# 3bpV2A_Opt.net
KiCad netlist of a schematic drawn in EAGLE
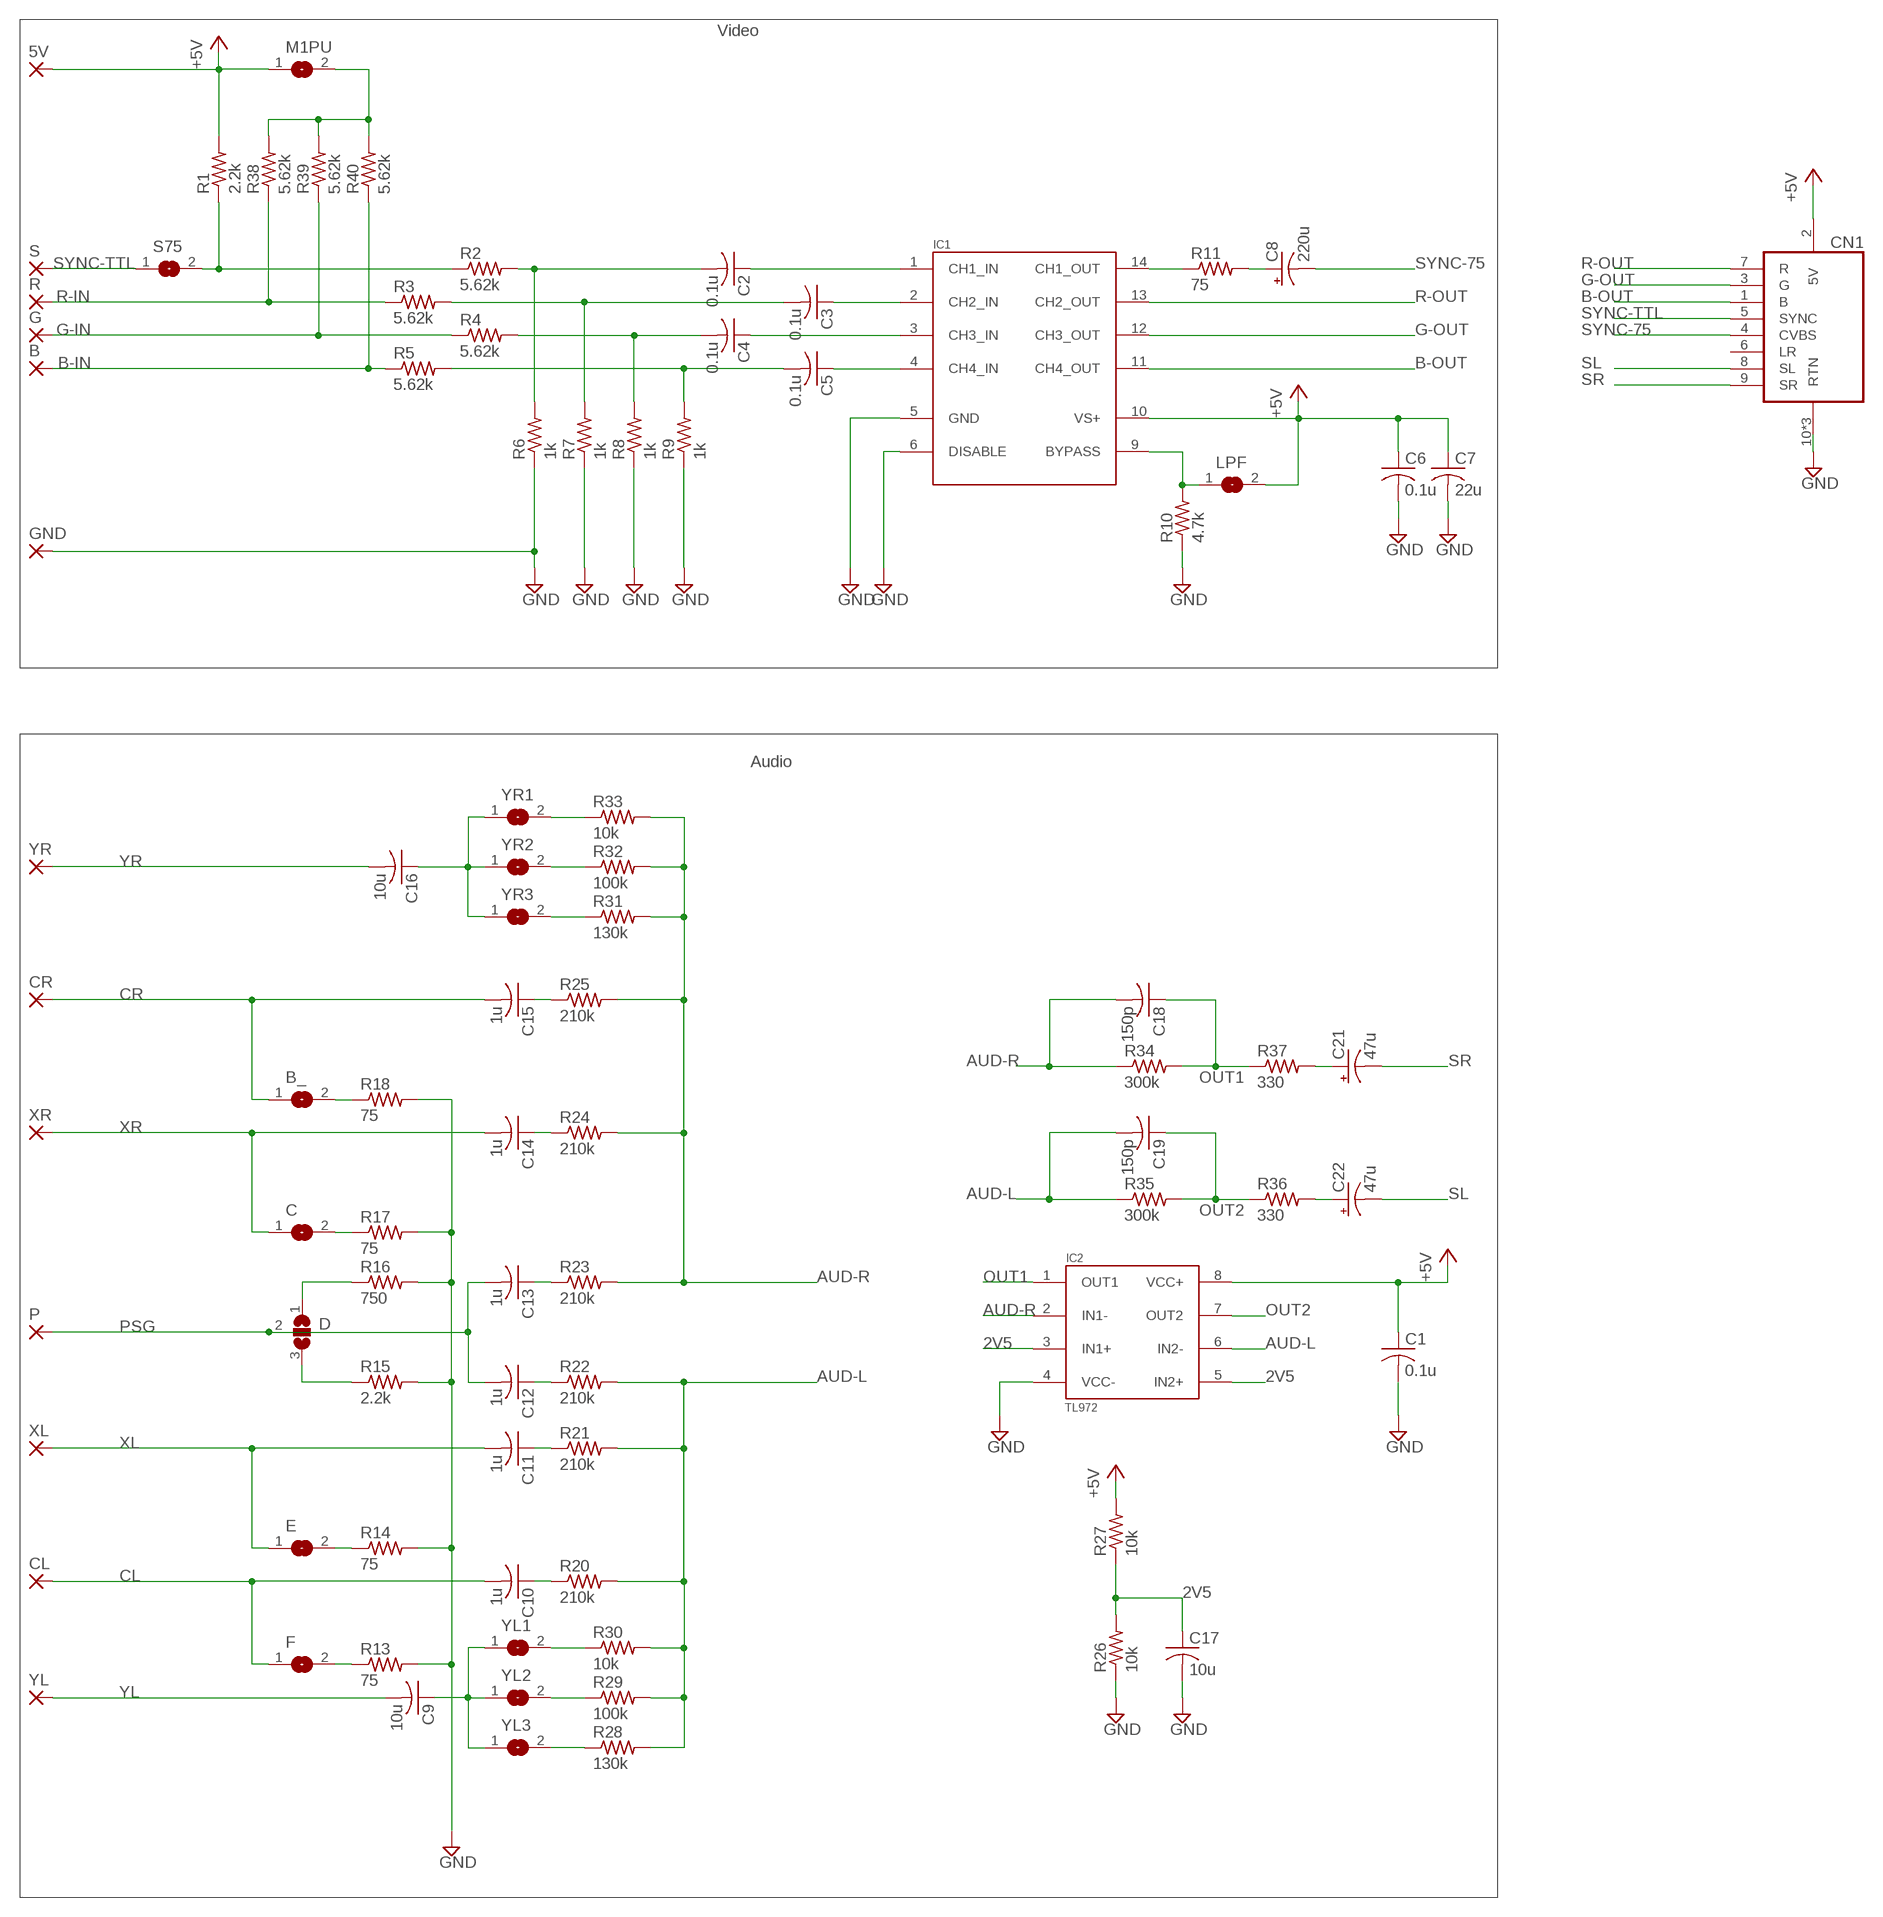
[diagram p0: schematic, sheet 1]

(export (version "E")
  (design (tool "Eeschema 10.0.6"))
  (components
    (comp (ref "5V")
      (value "SMD2")
      (footprint "eagle-import:SMD1,27-2,54")
      (libsource (lib "eagle-import") (part "SMD2"))
    )
    (comp (ref "B")
      (value "SMD2")
      (footprint "eagle-import:SMD1,27-2,54")
      (libsource (lib "eagle-import") (part "SMD2"))
    )
    (comp (ref "B_")
      (value "SMD_J")
      (footprint "eagle-import:SJ")
      (libsource (lib "eagle-import") (part "SMD_J"))
    )
    (comp (ref "C")
      (value "SMD_J")
      (footprint "eagle-import:SJ")
      (libsource (lib "eagle-import") (part "SMD_J"))
    )
    (comp (ref "C1")
      (value "0.1u")
      (footprint "eagle-import:C0603")
      (libsource (lib "eagle-import") (part "C-USC0603"))
    )
    (comp (ref "C2")
      (value "0.1u")
      (footprint "eagle-import:C0603")
      (libsource (lib "eagle-import") (part "C-USC0603"))
    )
    (comp (ref "C3")
      (value "0.1u")
      (footprint "eagle-import:C0603")
      (libsource (lib "eagle-import") (part "C-USC0603"))
    )
    (comp (ref "C4")
      (value "0.1u")
      (footprint "eagle-import:C0603")
      (libsource (lib "eagle-import") (part "C-USC0603"))
    )
    (comp (ref "C5")
      (value "0.1u")
      (footprint "eagle-import:C0603")
      (libsource (lib "eagle-import") (part "C-USC0603"))
    )
    (comp (ref "C6")
      (value "0.1u")
      (footprint "eagle-import:C0603")
      (libsource (lib "eagle-import") (part "C-USC0603"))
    )
    (comp (ref "C7")
      (value "22u")
      (footprint "eagle-import:C1206")
      (libsource (lib "eagle-import") (part "C-USC1206"))
    )
    (comp (ref "C8")
      (value "220u")
      (footprint "eagle-import:CT3528")
      (libsource (lib "eagle-import") (part "CPOL-USCT3528"))
    )
    (comp (ref "C9")
      (value "10u")
      (footprint "eagle-import:C0805")
      (libsource (lib "eagle-import") (part "C-USC0805"))
    )
    (comp (ref "C10")
      (value "1u")
      (footprint "eagle-import:C0603")
      (libsource (lib "eagle-import") (part "C-USC0603"))
    )
    (comp (ref "C11")
      (value "1u")
      (footprint "eagle-import:C0603")
      (libsource (lib "eagle-import") (part "C-USC0603"))
    )
    (comp (ref "C12")
      (value "1u")
      (footprint "eagle-import:C0603")
      (libsource (lib "eagle-import") (part "C-USC0603"))
    )
    (comp (ref "C13")
      (value "1u")
      (footprint "eagle-import:C0603")
      (libsource (lib "eagle-import") (part "C-USC0603"))
    )
    (comp (ref "C14")
      (value "1u")
      (footprint "eagle-import:C0603")
      (libsource (lib "eagle-import") (part "C-USC0603"))
    )
    (comp (ref "C15")
      (value "1u")
      (footprint "eagle-import:C0603")
      (libsource (lib "eagle-import") (part "C-USC0603"))
    )
    (comp (ref "C16")
      (value "10u")
      (footprint "eagle-import:C0805")
      (libsource (lib "eagle-import") (part "C-USC0805"))
    )
    (comp (ref "C17")
      (value "10u")
      (footprint "eagle-import:C1206")
      (libsource (lib "eagle-import") (part "C-USC1206"))
    )
    (comp (ref "C18")
      (value "150p")
      (footprint "eagle-import:C0603")
      (libsource (lib "eagle-import") (part "C-USC0603"))
    )
    (comp (ref "C19")
      (value "150p")
      (footprint "eagle-import:C0603")
      (libsource (lib "eagle-import") (part "C-USC0603"))
    )
    (comp (ref "C21")
      (value "47u")
      (footprint "eagle-import:CT3528")
      (libsource (lib "eagle-import") (part "CPOL-USCT3528"))
    )
    (comp (ref "C22")
      (value "47u")
      (footprint "eagle-import:CT3528")
      (libsource (lib "eagle-import") (part "CPOL-USCT3528"))
    )
    (comp (ref "CL")
      (value "SMD2")
      (footprint "eagle-import:SMD1,27-2,54")
      (libsource (lib "eagle-import") (part "SMD2"))
    )
    (comp (ref "CN1")
      (value "MD-90SM")
      (footprint "eagle-import:MD90SM")
      (libsource (lib "eagle-import") (part "MD-90SM"))
    )
    (comp (ref "CR")
      (value "SMD2")
      (footprint "eagle-import:SMD1,27-2,54")
      (libsource (lib "eagle-import") (part "SMD2"))
    )
    (comp (ref "D")
      (value "SMD_J2")
      (footprint "eagle-import:SJ_2")
      (libsource (lib "eagle-import") (part "SMD_J2"))
    )
    (comp (ref "E")
      (value "SMD_J")
      (footprint "eagle-import:SJ")
      (libsource (lib "eagle-import") (part "SMD_J"))
    )
    (comp (ref "F")
      (value "SMD_J")
      (footprint "eagle-import:SJ")
      (libsource (lib "eagle-import") (part "SMD_J"))
    )
    (comp (ref "G")
      (value "SMD2")
      (footprint "eagle-import:SMD1,27-2,54")
      (libsource (lib "eagle-import") (part "SMD2"))
    )
    (comp (ref "GND")
      (value "SMD2")
      (footprint "eagle-import:SMD1,27-2,54")
      (libsource (lib "eagle-import") (part "SMD2"))
    )
    (comp (ref "IC1")
      (value "THS7374IPWR")
      (footprint "eagle-import:TSSOP14")
      (libsource (lib "eagle-import") (part "THS7374IPWR"))
    )
    (comp (ref "IC2")
      (value "TL972")
      (footprint "eagle-import:SOIC8")
      (libsource (lib "eagle-import") (part "TL972"))
    )
    (comp (ref "LPF")
      (value "SMD_J")
      (footprint "eagle-import:SJ")
      (libsource (lib "eagle-import") (part "SMD_J"))
    )
    (comp (ref "M1PU")
      (value "SMD_J")
      (footprint "eagle-import:SJ")
      (libsource (lib "eagle-import") (part "SMD_J"))
    )
    (comp (ref "P")
      (value "SMD2")
      (footprint "eagle-import:SMD1,27-2,54")
      (libsource (lib "eagle-import") (part "SMD2"))
    )
    (comp (ref "R")
      (value "SMD2")
      (footprint "eagle-import:SMD1,27-2,54")
      (libsource (lib "eagle-import") (part "SMD2"))
    )
    (comp (ref "R1")
      (value "2.2k")
      (footprint "eagle-import:R0603")
      (libsource (lib "eagle-import") (part "R-US_R0603"))
    )
    (comp (ref "R2")
      (value "5.62k")
      (footprint "eagle-import:R0603")
      (libsource (lib "eagle-import") (part "R-US_R0603"))
    )
    (comp (ref "R3")
      (value "5.62k")
      (footprint "eagle-import:R0603")
      (libsource (lib "eagle-import") (part "R-US_R0603"))
    )
    (comp (ref "R4")
      (value "5.62k")
      (footprint "eagle-import:R0603")
      (libsource (lib "eagle-import") (part "R-US_R0603"))
    )
    (comp (ref "R5")
      (value "5.62k")
      (footprint "eagle-import:R0603")
      (libsource (lib "eagle-import") (part "R-US_R0603"))
    )
    (comp (ref "R6")
      (value "1k")
      (footprint "eagle-import:R0603")
      (libsource (lib "eagle-import") (part "R-US_R0603"))
    )
    (comp (ref "R7")
      (value "1k")
      (footprint "eagle-import:R0603")
      (libsource (lib "eagle-import") (part "R-US_R0603"))
    )
    (comp (ref "R8")
      (value "1k")
      (footprint "eagle-import:R0603")
      (libsource (lib "eagle-import") (part "R-US_R0603"))
    )
    (comp (ref "R9")
      (value "1k")
      (footprint "eagle-import:R0603")
      (libsource (lib "eagle-import") (part "R-US_R0603"))
    )
    (comp (ref "R10")
      (value "4.7k")
      (footprint "eagle-import:R0603")
      (libsource (lib "eagle-import") (part "R-US_R0603"))
    )
    (comp (ref "R11")
      (value "75")
      (footprint "eagle-import:R0603")
      (libsource (lib "eagle-import") (part "R-US_R0603"))
    )
    (comp (ref "R13")
      (value "75")
      (footprint "eagle-import:R0603")
      (libsource (lib "eagle-import") (part "R-US_R0603"))
    )
    (comp (ref "R14")
      (value "75")
      (footprint "eagle-import:R0603")
      (libsource (lib "eagle-import") (part "R-US_R0603"))
    )
    (comp (ref "R15")
      (value "2.2k")
      (footprint "eagle-import:R0603")
      (libsource (lib "eagle-import") (part "R-US_R0603"))
    )
    (comp (ref "R16")
      (value "750")
      (footprint "eagle-import:R0603")
      (libsource (lib "eagle-import") (part "R-US_R0603"))
    )
    (comp (ref "R17")
      (value "75")
      (footprint "eagle-import:R0603")
      (libsource (lib "eagle-import") (part "R-US_R0603"))
    )
    (comp (ref "R18")
      (value "75")
      (footprint "eagle-import:R0603")
      (libsource (lib "eagle-import") (part "R-US_R0603"))
    )
    (comp (ref "R20")
      (value "210k")
      (footprint "eagle-import:R0603")
      (libsource (lib "eagle-import") (part "R-US_R0603"))
    )
    (comp (ref "R21")
      (value "210k")
      (footprint "eagle-import:R0603")
      (libsource (lib "eagle-import") (part "R-US_R0603"))
    )
    (comp (ref "R22")
      (value "210k")
      (footprint "eagle-import:R0603")
      (libsource (lib "eagle-import") (part "R-US_R0603"))
    )
    (comp (ref "R23")
      (value "210k")
      (footprint "eagle-import:R0603")
      (libsource (lib "eagle-import") (part "R-US_R0603"))
    )
    (comp (ref "R24")
      (value "210k")
      (footprint "eagle-import:R0603")
      (libsource (lib "eagle-import") (part "R-US_R0603"))
    )
    (comp (ref "R25")
      (value "210k")
      (footprint "eagle-import:R0603")
      (libsource (lib "eagle-import") (part "R-US_R0603"))
    )
    (comp (ref "R26")
      (value "10k")
      (footprint "eagle-import:R0603")
      (libsource (lib "eagle-import") (part "R-US_R0603"))
    )
    (comp (ref "R27")
      (value "10k")
      (footprint "eagle-import:R0603")
      (libsource (lib "eagle-import") (part "R-US_R0603"))
    )
    (comp (ref "R28")
      (value "130k")
      (footprint "eagle-import:R0603")
      (libsource (lib "eagle-import") (part "R-US_R0603"))
    )
    (comp (ref "R29")
      (value "100k")
      (footprint "eagle-import:R0603")
      (libsource (lib "eagle-import") (part "R-US_R0603"))
    )
    (comp (ref "R30")
      (value "10k")
      (footprint "eagle-import:R0603")
      (libsource (lib "eagle-import") (part "R-US_R0603"))
    )
    (comp (ref "R31")
      (value "130k")
      (footprint "eagle-import:R0603")
      (libsource (lib "eagle-import") (part "R-US_R0603"))
    )
    (comp (ref "R32")
      (value "100k")
      (footprint "eagle-import:R0603")
      (libsource (lib "eagle-import") (part "R-US_R0603"))
    )
    (comp (ref "R33")
      (value "10k")
      (footprint "eagle-import:R0603")
      (libsource (lib "eagle-import") (part "R-US_R0603"))
    )
    (comp (ref "R34")
      (value "300k")
      (footprint "eagle-import:R0603")
      (libsource (lib "eagle-import") (part "R-US_R0603"))
    )
    (comp (ref "R35")
      (value "300k")
      (footprint "eagle-import:R0603")
      (libsource (lib "eagle-import") (part "R-US_R0603"))
    )
    (comp (ref "R36")
      (value "330")
      (footprint "eagle-import:R0603")
      (libsource (lib "eagle-import") (part "R-US_R0603"))
    )
    (comp (ref "R37")
      (value "330")
      (footprint "eagle-import:R0603")
      (libsource (lib "eagle-import") (part "R-US_R0603"))
    )
    (comp (ref "R38")
      (value "5.62k")
      (footprint "eagle-import:R0603")
      (libsource (lib "eagle-import") (part "R-US_R0603"))
    )
    (comp (ref "R39")
      (value "5.62k")
      (footprint "eagle-import:R0603")
      (libsource (lib "eagle-import") (part "R-US_R0603"))
    )
    (comp (ref "R40")
      (value "5.62k")
      (footprint "eagle-import:R0603")
      (libsource (lib "eagle-import") (part "R-US_R0603"))
    )
    (comp (ref "S")
      (value "SMD2")
      (footprint "eagle-import:SMD1,27-2,54")
      (libsource (lib "eagle-import") (part "SMD2"))
    )
    (comp (ref "S75")
      (value "SMD_J")
      (footprint "eagle-import:SJ")
      (libsource (lib "eagle-import") (part "SMD_J"))
    )
    (comp (ref "XL")
      (value "SMD2")
      (footprint "eagle-import:SMD1,27-2,54")
      (libsource (lib "eagle-import") (part "SMD2"))
    )
    (comp (ref "XR")
      (value "SMD2")
      (footprint "eagle-import:SMD1,27-2,54")
      (libsource (lib "eagle-import") (part "SMD2"))
    )
    (comp (ref "YL")
      (value "SMD2")
      (footprint "eagle-import:SMD1,27-2,54")
      (libsource (lib "eagle-import") (part "SMD2"))
    )
    (comp (ref "YL1")
      (value "SMD_J")
      (footprint "eagle-import:SJ")
      (libsource (lib "eagle-import") (part "SMD_J"))
    )
    (comp (ref "YL2")
      (value "SMD_J")
      (footprint "eagle-import:SJ")
      (libsource (lib "eagle-import") (part "SMD_J"))
    )
    (comp (ref "YL3")
      (value "SMD_J")
      (footprint "eagle-import:SJ")
      (libsource (lib "eagle-import") (part "SMD_J"))
    )
    (comp (ref "YR")
      (value "SMD2")
      (footprint "eagle-import:SMD1,27-2,54")
      (libsource (lib "eagle-import") (part "SMD2"))
    )
    (comp (ref "YR1")
      (value "SMD_J")
      (footprint "eagle-import:SJ")
      (libsource (lib "eagle-import") (part "SMD_J"))
    )
    (comp (ref "YR2")
      (value "SMD_J")
      (footprint "eagle-import:SJ")
      (libsource (lib "eagle-import") (part "SMD_J"))
    )
    (comp (ref "YR3")
      (value "SMD_J")
      (footprint "eagle-import:SJ")
      (libsource (lib "eagle-import") (part "SMD_J"))
    )
  )
  (nets
    (net (code "1") (name "+5V") (class "Default")
      (node (ref "5V") (pin "1") (pinfunction "P_1") (pintype "passive"))
      (node (ref "C1") (pin "1") (pinfunction "1_1") (pintype "passive"))
      (node (ref "C6") (pin "1") (pinfunction "1_1") (pintype "passive"))
      (node (ref "C7") (pin "1") (pinfunction "1_1") (pintype "passive"))
      (node (ref "CN1") (pin "2") (pinfunction "5V_2") (pintype "bidirectional"))
      (node (ref "IC1") (pin "10") (pinfunction "VS+_10") (pintype "bidirectional"))
      (node (ref "IC2") (pin "8") (pinfunction "VCC+_8") (pintype "bidirectional"))
      (node (ref "LPF") (pin "2") (pinfunction "2_2") (pintype "passive"))
      (node (ref "M1PU") (pin "1") (pinfunction "1_1") (pintype "passive"))
      (node (ref "R1") (pin "2") (pinfunction "2_2") (pintype "passive"))
      (node (ref "R27") (pin "2") (pinfunction "2_2") (pintype "passive"))
    )
    (net (code "2") (name "/2V5") (class "Default")
      (node (ref "C17") (pin "1") (pinfunction "1_1") (pintype "passive"))
      (node (ref "IC2") (pin "3") (pinfunction "IN1+_3") (pintype "bidirectional"))
      (node (ref "IC2") (pin "5") (pinfunction "IN2+_5") (pintype "bidirectional"))
      (node (ref "R26") (pin "2") (pinfunction "2_2") (pintype "passive"))
      (node (ref "R27") (pin "1") (pinfunction "1_1") (pintype "passive"))
    )
    (net (code "3") (name "/AUD-L") (class "Default")
      (node (ref "C19") (pin "2") (pinfunction "2_2") (pintype "passive"))
      (node (ref "IC2") (pin "6") (pinfunction "IN2-_6") (pintype "bidirectional"))
      (node (ref "R20") (pin "2") (pinfunction "2_2") (pintype "passive"))
      (node (ref "R21") (pin "2") (pinfunction "2_2") (pintype "passive"))
      (node (ref "R22") (pin "2") (pinfunction "2_2") (pintype "passive"))
      (node (ref "R28") (pin "2") (pinfunction "2_2") (pintype "passive"))
      (node (ref "R29") (pin "2") (pinfunction "2_2") (pintype "passive"))
      (node (ref "R30") (pin "2") (pinfunction "2_2") (pintype "passive"))
      (node (ref "R35") (pin "1") (pinfunction "1_1") (pintype "passive"))
    )
    (net (code "4") (name "/AUD-R") (class "Default")
      (node (ref "C18") (pin "2") (pinfunction "2_2") (pintype "passive"))
      (node (ref "IC2") (pin "2") (pinfunction "IN1-_2") (pintype "bidirectional"))
      (node (ref "R23") (pin "2") (pinfunction "2_2") (pintype "passive"))
      (node (ref "R24") (pin "2") (pinfunction "2_2") (pintype "passive"))
      (node (ref "R25") (pin "2") (pinfunction "2_2") (pintype "passive"))
      (node (ref "R31") (pin "2") (pinfunction "2_2") (pintype "passive"))
      (node (ref "R32") (pin "2") (pinfunction "2_2") (pintype "passive"))
      (node (ref "R33") (pin "2") (pinfunction "2_2") (pintype "passive"))
      (node (ref "R34") (pin "1") (pinfunction "1_1") (pintype "passive"))
    )
    (net (code "5") (name "/B-IN") (class "Default")
      (node (ref "B") (pin "1") (pinfunction "P_1") (pintype "passive"))
      (node (ref "R40") (pin "1") (pinfunction "1_1") (pintype "passive"))
      (node (ref "R5") (pin "1") (pinfunction "1_1") (pintype "passive"))
    )
    (net (code "6") (name "/B-OUT") (class "Default")
      (node (ref "CN1") (pin "1") (pinfunction "B_1") (pintype "bidirectional"))
      (node (ref "IC1") (pin "11") (pinfunction "CH4_OUT_11") (pintype "bidirectional"))
    )
    (net (code "7") (name "/CL") (class "Default")
      (node (ref "C10") (pin "2") (pinfunction "2_2") (pintype "passive"))
      (node (ref "CL") (pin "1") (pinfunction "P_1") (pintype "passive"))
      (node (ref "F") (pin "1") (pinfunction "1_1") (pintype "passive"))
    )
    (net (code "8") (name "/CR") (class "Default")
      (node (ref "B_") (pin "1") (pinfunction "1_1") (pintype "passive"))
      (node (ref "C15") (pin "2") (pinfunction "2_2") (pintype "passive"))
      (node (ref "CR") (pin "1") (pinfunction "P_1") (pintype "passive"))
    )
    (net (code "9") (name "/G-IN") (class "Default")
      (node (ref "G") (pin "1") (pinfunction "P_1") (pintype "passive"))
      (node (ref "R39") (pin "1") (pinfunction "1_1") (pintype "passive"))
      (node (ref "R4") (pin "1") (pinfunction "1_1") (pintype "passive"))
    )
    (net (code "10") (name "/G-OUT") (class "Default")
      (node (ref "CN1") (pin "3") (pinfunction "G_3") (pintype "bidirectional"))
      (node (ref "IC1") (pin "12") (pinfunction "CH3_OUT_12") (pintype "bidirectional"))
    )
    (net (code "11") (name "/OUT1") (class "Default")
      (node (ref "C18") (pin "1") (pinfunction "1_1") (pintype "passive"))
      (node (ref "IC2") (pin "1") (pinfunction "OUT1_1") (pintype "bidirectional"))
      (node (ref "R34") (pin "2") (pinfunction "2_2") (pintype "passive"))
      (node (ref "R37") (pin "1") (pinfunction "1_1") (pintype "passive"))
    )
    (net (code "12") (name "/OUT2") (class "Default")
      (node (ref "C19") (pin "1") (pinfunction "1_1") (pintype "passive"))
      (node (ref "IC2") (pin "7") (pinfunction "OUT2_7") (pintype "bidirectional"))
      (node (ref "R35") (pin "2") (pinfunction "2_2") (pintype "passive"))
      (node (ref "R36") (pin "1") (pinfunction "1_1") (pintype "passive"))
    )
    (net (code "13") (name "/PSG") (class "Default")
      (node (ref "C12") (pin "2") (pinfunction "2_2") (pintype "passive"))
      (node (ref "C13") (pin "2") (pinfunction "2_2") (pintype "passive"))
      (node (ref "D") (pin "2") (pinfunction "2_2") (pintype "passive"))
      (node (ref "P") (pin "1") (pinfunction "P_1") (pintype "passive"))
    )
    (net (code "14") (name "/R-IN") (class "Default")
      (node (ref "R") (pin "1") (pinfunction "P_1") (pintype "passive"))
      (node (ref "R3") (pin "1") (pinfunction "1_1") (pintype "passive"))
      (node (ref "R38") (pin "1") (pinfunction "1_1") (pintype "passive"))
    )
    (net (code "15") (name "/R-OUT") (class "Default")
      (node (ref "CN1") (pin "7") (pinfunction "R_7") (pintype "bidirectional"))
      (node (ref "IC1") (pin "13") (pinfunction "CH2_OUT_13") (pintype "bidirectional"))
    )
    (net (code "16") (name "/SL") (class "Default")
      (node (ref "C22") (pin "-") (pinfunction "-_-") (pintype "passive"))
      (node (ref "CN1") (pin "8") (pinfunction "SL_8") (pintype "bidirectional"))
    )
    (net (code "17") (name "/SR") (class "Default")
      (node (ref "C21") (pin "-") (pinfunction "-_-") (pintype "passive"))
      (node (ref "CN1") (pin "9") (pinfunction "SR_9") (pintype "bidirectional"))
    )
    (net (code "18") (name "/SYNC-75") (class "Default")
      (node (ref "C8") (pin "-") (pinfunction "-_-") (pintype "passive"))
      (node (ref "CN1") (pin "4") (pinfunction "CVBS_4") (pintype "bidirectional"))
    )
    (net (code "19") (name "/SYNC-TTL") (class "Default")
      (node (ref "CN1") (pin "5") (pinfunction "SYNC_5") (pintype "bidirectional"))
      (node (ref "S") (pin "1") (pinfunction "P_1") (pintype "passive"))
      (node (ref "S75") (pin "1") (pinfunction "1_1") (pintype "passive"))
    )
    (net (code "20") (name "/XL") (class "Default")
      (node (ref "C11") (pin "2") (pinfunction "2_2") (pintype "passive"))
      (node (ref "E") (pin "1") (pinfunction "1_1") (pintype "passive"))
      (node (ref "XL") (pin "1") (pinfunction "P_1") (pintype "passive"))
    )
    (net (code "21") (name "/XR") (class "Default")
      (node (ref "C") (pin "1") (pinfunction "1_1") (pintype "passive"))
      (node (ref "C14") (pin "2") (pinfunction "2_2") (pintype "passive"))
      (node (ref "XR") (pin "1") (pinfunction "P_1") (pintype "passive"))
    )
    (net (code "22") (name "/YL") (class "Default")
      (node (ref "C9") (pin "2") (pinfunction "2_2") (pintype "passive"))
      (node (ref "YL") (pin "1") (pinfunction "P_1") (pintype "passive"))
    )
    (net (code "23") (name "/YR") (class "Default")
      (node (ref "C16") (pin "2") (pinfunction "2_2") (pintype "passive"))
      (node (ref "YR") (pin "1") (pinfunction "P_1") (pintype "passive"))
    )
    (net (code "24") (name "GND") (class "Default")
      (node (ref "C1") (pin "2") (pinfunction "2_2") (pintype "passive"))
      (node (ref "C17") (pin "2") (pinfunction "2_2") (pintype "passive"))
      (node (ref "C6") (pin "2") (pinfunction "2_2") (pintype "passive"))
      (node (ref "C7") (pin "2") (pinfunction "2_2") (pintype "passive"))
      (node (ref "CN1") (pin "10") (pinfunction "RTN_10") (pintype "bidirectional"))
      (node (ref "CN1") (pin "11") (pinfunction "RTN_11") (pintype "bidirectional"))
      (node (ref "CN1") (pin "12") (pinfunction "RTN_12") (pintype "bidirectional"))
      (node (ref "GND") (pin "1") (pinfunction "P_1") (pintype "passive"))
      (node (ref "IC1") (pin "5") (pinfunction "GND_5") (pintype "bidirectional"))
      (node (ref "IC1") (pin "6") (pinfunction "DISABLE_6") (pintype "bidirectional"))
      (node (ref "IC2") (pin "4") (pinfunction "VCC-_4") (pintype "bidirectional"))
      (node (ref "R10") (pin "1") (pinfunction "1_1") (pintype "passive"))
      (node (ref "R13") (pin "2") (pinfunction "2_2") (pintype "passive"))
      (node (ref "R14") (pin "2") (pinfunction "2_2") (pintype "passive"))
      (node (ref "R15") (pin "2") (pinfunction "2_2") (pintype "passive"))
      (node (ref "R16") (pin "2") (pinfunction "2_2") (pintype "passive"))
      (node (ref "R17") (pin "2") (pinfunction "2_2") (pintype "passive"))
      (node (ref "R18") (pin "2") (pinfunction "2_2") (pintype "passive"))
      (node (ref "R26") (pin "1") (pinfunction "1_1") (pintype "passive"))
      (node (ref "R6") (pin "1") (pinfunction "1_1") (pintype "passive"))
      (node (ref "R7") (pin "1") (pinfunction "1_1") (pintype "passive"))
      (node (ref "R8") (pin "1") (pinfunction "1_1") (pintype "passive"))
      (node (ref "R9") (pin "1") (pinfunction "1_1") (pintype "passive"))
    )
    (net (code "25") (name "Net-(B_-Pad2)") (class "Default")
      (node (ref "B_") (pin "2") (pinfunction "2_2") (pintype "passive"))
      (node (ref "R18") (pin "1") (pinfunction "1_1") (pintype "passive"))
    )
    (net (code "26") (name "Net-(C-Pad2)") (class "Default")
      (node (ref "C") (pin "2") (pinfunction "2_2") (pintype "passive"))
      (node (ref "R17") (pin "1") (pinfunction "1_1") (pintype "passive"))
    )
    (net (code "27") (name "Net-(C2-Pad2)") (class "Default")
      (node (ref "C2") (pin "2") (pinfunction "2_2") (pintype "passive"))
      (node (ref "R2") (pin "2") (pinfunction "2_2") (pintype "passive"))
      (node (ref "R6") (pin "2") (pinfunction "2_2") (pintype "passive"))
    )
    (net (code "28") (name "Net-(C3-Pad2)") (class "Default")
      (node (ref "C3") (pin "2") (pinfunction "2_2") (pintype "passive"))
      (node (ref "R3") (pin "2") (pinfunction "2_2") (pintype "passive"))
      (node (ref "R7") (pin "2") (pinfunction "2_2") (pintype "passive"))
    )
    (net (code "29") (name "Net-(C4-Pad2)") (class "Default")
      (node (ref "C4") (pin "2") (pinfunction "2_2") (pintype "passive"))
      (node (ref "R4") (pin "2") (pinfunction "2_2") (pintype "passive"))
      (node (ref "R8") (pin "2") (pinfunction "2_2") (pintype "passive"))
    )
    (net (code "30") (name "Net-(C5-Pad2)") (class "Default")
      (node (ref "C5") (pin "2") (pinfunction "2_2") (pintype "passive"))
      (node (ref "R5") (pin "2") (pinfunction "2_2") (pintype "passive"))
      (node (ref "R9") (pin "2") (pinfunction "2_2") (pintype "passive"))
    )
    (net (code "31") (name "Net-(C8-Pad+)") (class "Default")
      (node (ref "C8") (pin "+") (pinfunction "+_+") (pintype "passive"))
      (node (ref "R11") (pin "2") (pinfunction "2_2") (pintype "passive"))
    )
    (net (code "32") (name "Net-(C9-Pad1)") (class "Default")
      (node (ref "C9") (pin "1") (pinfunction "1_1") (pintype "passive"))
      (node (ref "YL1") (pin "1") (pinfunction "1_1") (pintype "passive"))
      (node (ref "YL2") (pin "1") (pinfunction "1_1") (pintype "passive"))
      (node (ref "YL3") (pin "1") (pinfunction "1_1") (pintype "passive"))
    )
    (net (code "33") (name "Net-(C10-Pad1)") (class "Default")
      (node (ref "C10") (pin "1") (pinfunction "1_1") (pintype "passive"))
      (node (ref "R20") (pin "1") (pinfunction "1_1") (pintype "passive"))
    )
    (net (code "34") (name "Net-(C11-Pad1)") (class "Default")
      (node (ref "C11") (pin "1") (pinfunction "1_1") (pintype "passive"))
      (node (ref "R21") (pin "1") (pinfunction "1_1") (pintype "passive"))
    )
    (net (code "35") (name "Net-(C12-Pad1)") (class "Default")
      (node (ref "C12") (pin "1") (pinfunction "1_1") (pintype "passive"))
      (node (ref "R22") (pin "1") (pinfunction "1_1") (pintype "passive"))
    )
    (net (code "36") (name "Net-(C13-Pad1)") (class "Default")
      (node (ref "C13") (pin "1") (pinfunction "1_1") (pintype "passive"))
      (node (ref "R23") (pin "1") (pinfunction "1_1") (pintype "passive"))
    )
    (net (code "37") (name "Net-(C14-Pad1)") (class "Default")
      (node (ref "C14") (pin "1") (pinfunction "1_1") (pintype "passive"))
      (node (ref "R24") (pin "1") (pinfunction "1_1") (pintype "passive"))
    )
    (net (code "38") (name "Net-(C15-Pad1)") (class "Default")
      (node (ref "C15") (pin "1") (pinfunction "1_1") (pintype "passive"))
      (node (ref "R25") (pin "1") (pinfunction "1_1") (pintype "passive"))
    )
    (net (code "39") (name "Net-(C16-Pad1)") (class "Default")
      (node (ref "C16") (pin "1") (pinfunction "1_1") (pintype "passive"))
      (node (ref "YR1") (pin "1") (pinfunction "1_1") (pintype "passive"))
      (node (ref "YR2") (pin "1") (pinfunction "1_1") (pintype "passive"))
      (node (ref "YR3") (pin "1") (pinfunction "1_1") (pintype "passive"))
    )
    (net (code "40") (name "Net-(C21-Pad+)") (class "Default")
      (node (ref "C21") (pin "+") (pinfunction "+_+") (pintype "passive"))
      (node (ref "R37") (pin "2") (pinfunction "2_2") (pintype "passive"))
    )
    (net (code "41") (name "Net-(C22-Pad+)") (class "Default")
      (node (ref "C22") (pin "+") (pinfunction "+_+") (pintype "passive"))
      (node (ref "R36") (pin "2") (pinfunction "2_2") (pintype "passive"))
    )
    (net (code "42") (name "Net-(D-Pad1)") (class "Default")
      (node (ref "D") (pin "1") (pinfunction "1_1") (pintype "passive"))
      (node (ref "R16") (pin "1") (pinfunction "1_1") (pintype "passive"))
    )
    (net (code "43") (name "Net-(D-Pad3)") (class "Default")
      (node (ref "D") (pin "3") (pinfunction "3_3") (pintype "passive"))
      (node (ref "R15") (pin "1") (pinfunction "1_1") (pintype "passive"))
    )
    (net (code "44") (name "Net-(E-Pad2)") (class "Default")
      (node (ref "E") (pin "2") (pinfunction "2_2") (pintype "passive"))
      (node (ref "R14") (pin "1") (pinfunction "1_1") (pintype "passive"))
    )
    (net (code "45") (name "Net-(F-Pad2)") (class "Default")
      (node (ref "F") (pin "2") (pinfunction "2_2") (pintype "passive"))
      (node (ref "R13") (pin "1") (pinfunction "1_1") (pintype "passive"))
    )
    (net (code "46") (name "Net-(IC1-BYPASS)") (class "Default")
      (node (ref "IC1") (pin "9") (pinfunction "BYPASS_9") (pintype "bidirectional"))
      (node (ref "LPF") (pin "1") (pinfunction "1_1") (pintype "passive"))
      (node (ref "R10") (pin "2") (pinfunction "2_2") (pintype "passive"))
    )
    (net (code "47") (name "Net-(IC1-CH1_IN)") (class "Default")
      (node (ref "C2") (pin "1") (pinfunction "1_1") (pintype "passive"))
      (node (ref "IC1") (pin "1") (pinfunction "CH1_IN_1") (pintype "bidirectional"))
    )
    (net (code "48") (name "Net-(IC1-CH1_OUT)") (class "Default")
      (node (ref "IC1") (pin "14") (pinfunction "CH1_OUT_14") (pintype "bidirectional"))
      (node (ref "R11") (pin "1") (pinfunction "1_1") (pintype "passive"))
    )
    (net (code "49") (name "Net-(IC1-CH2_IN)") (class "Default")
      (node (ref "C3") (pin "1") (pinfunction "1_1") (pintype "passive"))
      (node (ref "IC1") (pin "2") (pinfunction "CH2_IN_2") (pintype "bidirectional"))
    )
    (net (code "50") (name "Net-(IC1-CH3_IN)") (class "Default")
      (node (ref "C4") (pin "1") (pinfunction "1_1") (pintype "passive"))
      (node (ref "IC1") (pin "3") (pinfunction "CH3_IN_3") (pintype "bidirectional"))
    )
    (net (code "51") (name "Net-(IC1-CH4_IN)") (class "Default")
      (node (ref "C5") (pin "1") (pinfunction "1_1") (pintype "passive"))
      (node (ref "IC1") (pin "4") (pinfunction "CH4_IN_4") (pintype "bidirectional"))
    )
    (net (code "52") (name "Net-(M1PU-Pad2)") (class "Default")
      (node (ref "M1PU") (pin "2") (pinfunction "2_2") (pintype "passive"))
      (node (ref "R38") (pin "2") (pinfunction "2_2") (pintype "passive"))
      (node (ref "R39") (pin "2") (pinfunction "2_2") (pintype "passive"))
      (node (ref "R40") (pin "2") (pinfunction "2_2") (pintype "passive"))
    )
    (net (code "53") (name "Net-(R1-Pad1)") (class "Default")
      (node (ref "R1") (pin "1") (pinfunction "1_1") (pintype "passive"))
      (node (ref "R2") (pin "1") (pinfunction "1_1") (pintype "passive"))
      (node (ref "S75") (pin "2") (pinfunction "2_2") (pintype "passive"))
    )
    (net (code "54") (name "Net-(R28-Pad1)") (class "Default")
      (node (ref "R28") (pin "1") (pinfunction "1_1") (pintype "passive"))
      (node (ref "YL3") (pin "2") (pinfunction "2_2") (pintype "passive"))
    )
    (net (code "55") (name "Net-(R29-Pad1)") (class "Default")
      (node (ref "R29") (pin "1") (pinfunction "1_1") (pintype "passive"))
      (node (ref "YL2") (pin "2") (pinfunction "2_2") (pintype "passive"))
    )
    (net (code "56") (name "Net-(R30-Pad1)") (class "Default")
      (node (ref "R30") (pin "1") (pinfunction "1_1") (pintype "passive"))
      (node (ref "YL1") (pin "2") (pinfunction "2_2") (pintype "passive"))
    )
    (net (code "57") (name "Net-(R31-Pad1)") (class "Default")
      (node (ref "R31") (pin "1") (pinfunction "1_1") (pintype "passive"))
      (node (ref "YR3") (pin "2") (pinfunction "2_2") (pintype "passive"))
    )
    (net (code "58") (name "Net-(R32-Pad1)") (class "Default")
      (node (ref "R32") (pin "1") (pinfunction "1_1") (pintype "passive"))
      (node (ref "YR2") (pin "2") (pinfunction "2_2") (pintype "passive"))
    )
    (net (code "59") (name "Net-(R33-Pad1)") (class "Default")
      (node (ref "R33") (pin "1") (pinfunction "1_1") (pintype "passive"))
      (node (ref "YR1") (pin "2") (pinfunction "2_2") (pintype "passive"))
    )
    (net (code "60") (name "unconnected-(CN1-LR-Pad6)") (class "Default")
      (node (ref "CN1") (pin "6") (pinfunction "LR_6") (pintype "bidirectional"))
    )
  )
)
